# PLD_AVR_Watchdog.net
KiCad netlist of a schematic drawn in Altium Designer
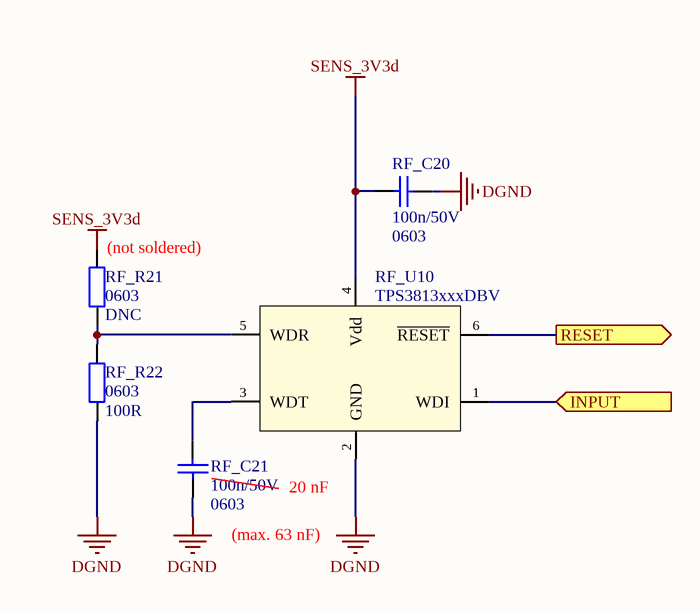
[diagram p0: PLD_AVR_Watchdog.SchDoc]

(export (version "E")
  (design (tool "Eeschema 10.0.6"))
  (components
    (comp (ref "RF_C20")
      (value "100n/50V")
      (footprint "SMD_Capacitor_0603")
      (description "Ceramic Cap Kemet COTS 100n/50V X7R 0603")
      (fields
        (field (name "MANUFACTURER") "Kemet")
        (field (name "MANUFACTURERPARTNUMBER") "C0603T104K5RALTU")
        (field (name "PACKAGE") "0603")
      )
      (libsource (lib "capacitors") (part "Cer_C0603T104K5RALTU"))
    )
    (comp (ref "RF_C21")
      (value "100n/50V")
      (footprint "SMD_Capacitor_0603")
      (description "Ceramic Cap Kemet COTS 100n/50V X7R 0603")
      (fields
        (field (name "MANUFACTURER") "Kemet")
        (field (name "MANUFACTURERPARTNUMBER") "C0603T104K5RALTU")
        (field (name "PACKAGE") "0603")
      )
      (libsource (lib "capacitors") (part "Cer_C0603T104K5RALTU"))
    )
    (comp (ref "RF_R21")
      (value "0603")
      (footprint "SMD_Resistor_0603")
      (description "Resistor")
      (fields (field (name "ALTIUM_VALUE") "DNC") (field (name "PUBLISHER") "Altium Limited"))
      (libsource (lib "Miscellaneous Devices") (part "Res2"))
    )
    (comp (ref "RF_R22")
      (value "0603")
      (footprint "SMD_Resistor_0603")
      (description "Resistor")
      (fields (field (name "ALTIUM_VALUE") "100R") (field (name "PUBLISHER") "Altium Limited"))
      (libsource (lib "Miscellaneous Devices") (part "Res2"))
    )
    (comp (ref "RF_U10")
      (value "TPS3813xxxDBV")
      (footprint "SOT23-6")
      (description "Processor Supervisory Circuits with Window-Watchdog.")
      (fields (field (name "MANUFACTURER") "Texas Instruments"))
      (libsource (lib "microcircuits_other-functions") (part "TPS3813xxxDBV"))
    )
  )
  (nets
    (net (code "1") (name "/INPUT") (class "Default")
      (node (ref "RF_U10") (pin "1") (pinfunction "WDI_1") (pintype "passive"))
    )
    (net (code "2") (name "/RESET") (class "Default")
      (node (ref "RF_U10") (pin "6") (pinfunction "~{RESET}_6") (pintype "passive"))
    )
    (net (code "3") (name "DGND") (class "Default")
      (node (ref "RF_C20") (pin "2") (pinfunction "2_2") (pintype "passive"))
      (node (ref "RF_C21") (pin "2") (pinfunction "2_2") (pintype "passive"))
      (node (ref "RF_R22") (pin "1") (pinfunction "1_1") (pintype "passive"))
      (node (ref "RF_U10") (pin "2") (pinfunction "GND_2") (pintype "passive"))
    )
    (net (code "4") (name "Net-(RF_U10-WDR)") (class "Default")
      (node (ref "RF_R21") (pin "1") (pinfunction "1_1") (pintype "passive"))
      (node (ref "RF_R22") (pin "2") (pinfunction "2_2") (pintype "passive"))
      (node (ref "RF_U10") (pin "5") (pinfunction "WDR_5") (pintype "passive"))
    )
    (net (code "5") (name "Net-(RF_U10-WDT)") (class "Default")
      (node (ref "RF_C21") (pin "1") (pinfunction "1_1") (pintype "passive"))
      (node (ref "RF_U10") (pin "3") (pinfunction "WDT_3") (pintype "passive"))
    )
    (net (code "6") (name "SENS_3V3d") (class "Default")
      (node (ref "RF_C20") (pin "1") (pinfunction "1_1") (pintype "passive"))
      (node (ref "RF_R21") (pin "2") (pinfunction "2_2") (pintype "passive"))
      (node (ref "RF_U10") (pin "4") (pinfunction "Vdd_4") (pintype "passive"))
    )
  )
)
